# power.net
KiCad netlist of a schematic drawn in Altium Designer
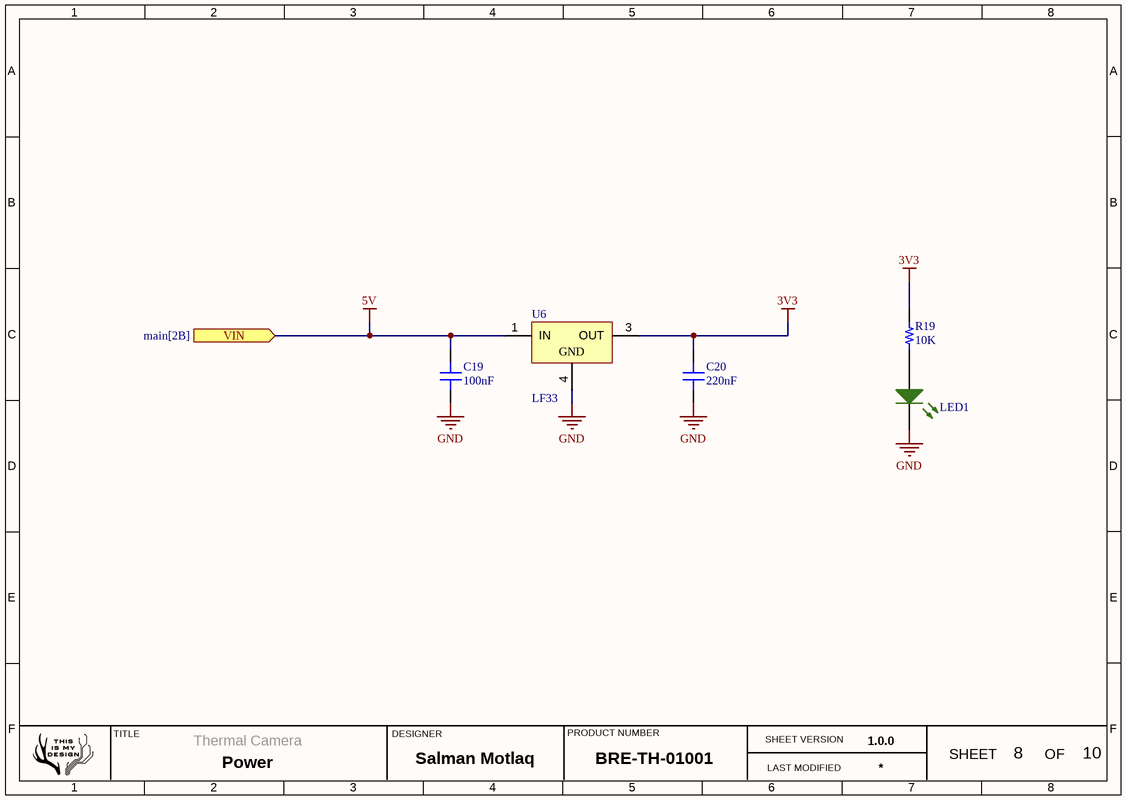
[diagram p0: power.SchDoc]

(export (version "E")
  (design (tool "Eeschema 10.0.6"))
  (components
    (comp (ref "C19")
      (value "100nF")
      (footprint "CAP 0603_1608")
      (description "SMT Capacitor")
      (libsource (lib "Capacitor") (part "Cap 0603"))
    )
    (comp (ref "C20")
      (value "220nF")
      (footprint "CAP 0603_1608")
      (description "SMT Capacitor")
      (libsource (lib "Capacitor") (part "Cap 0603"))
    )
    (comp (ref "LED1")
      (value "LED SMD 0603 GREEN")
      (footprint "LED_0603_GREEN")
      (libsource (lib "Led") (part "LED SMD 0603 GREEN"))
    )
    (comp (ref "R19")
      (value "10K")
      (footprint "RES 0603_1608")
      (description "SMT Resistor")
      (libsource (lib "Resistor") (part "Res 0603"))
    )
    (comp (ref "U6")
      (value "LF33")
      (footprint "TO-252")
      (description "500mA, Very Low Drop (0.45V) Voltage Regulator, 3.3V, 3-Pin DPAK, Tape and Reel")
      (fields (field (name "PARTNUMBER") "LF33CDT-TR"))
      (libsource (lib "Chip") (part "LF33 (SMD)"))
    )
  )
  (nets
    (net (code "1") (name "3V3") (class "Default")
      (node (ref "C20") (pin "2") (pinfunction "2_2") (pintype "passive"))
      (node (ref "R19") (pin "1") (pinfunction "1_1") (pintype "passive"))
      (node (ref "U6") (pin "3") (pinfunction "OUT_3") (pintype "power_in"))
    )
    (net (code "2") (name "5V") (class "Default")
      (node (ref "C19") (pin "2") (pinfunction "2_2") (pintype "passive"))
      (node (ref "U6") (pin "1") (pinfunction "IN_1") (pintype "power_in"))
    )
    (net (code "3") (name "GND") (class "Default")
      (node (ref "C19") (pin "1") (pinfunction "1_1") (pintype "passive"))
      (node (ref "C20") (pin "1") (pinfunction "1_1") (pintype "passive"))
      (node (ref "LED1") (pin "2") (pinfunction "K_2") (pintype "passive"))
      (node (ref "U6") (pin "4") (pinfunction "GND_4") (pintype "power_in"))
    )
    (net (code "4") (name "Net-(LED1-A)") (class "Default")
      (node (ref "LED1") (pin "1") (pinfunction "A_1") (pintype "passive"))
      (node (ref "R19") (pin "2") (pinfunction "2_2") (pintype "passive"))
    )
  )
)
